# MCU.net
KiCad netlist of a schematic drawn in Altium Designer
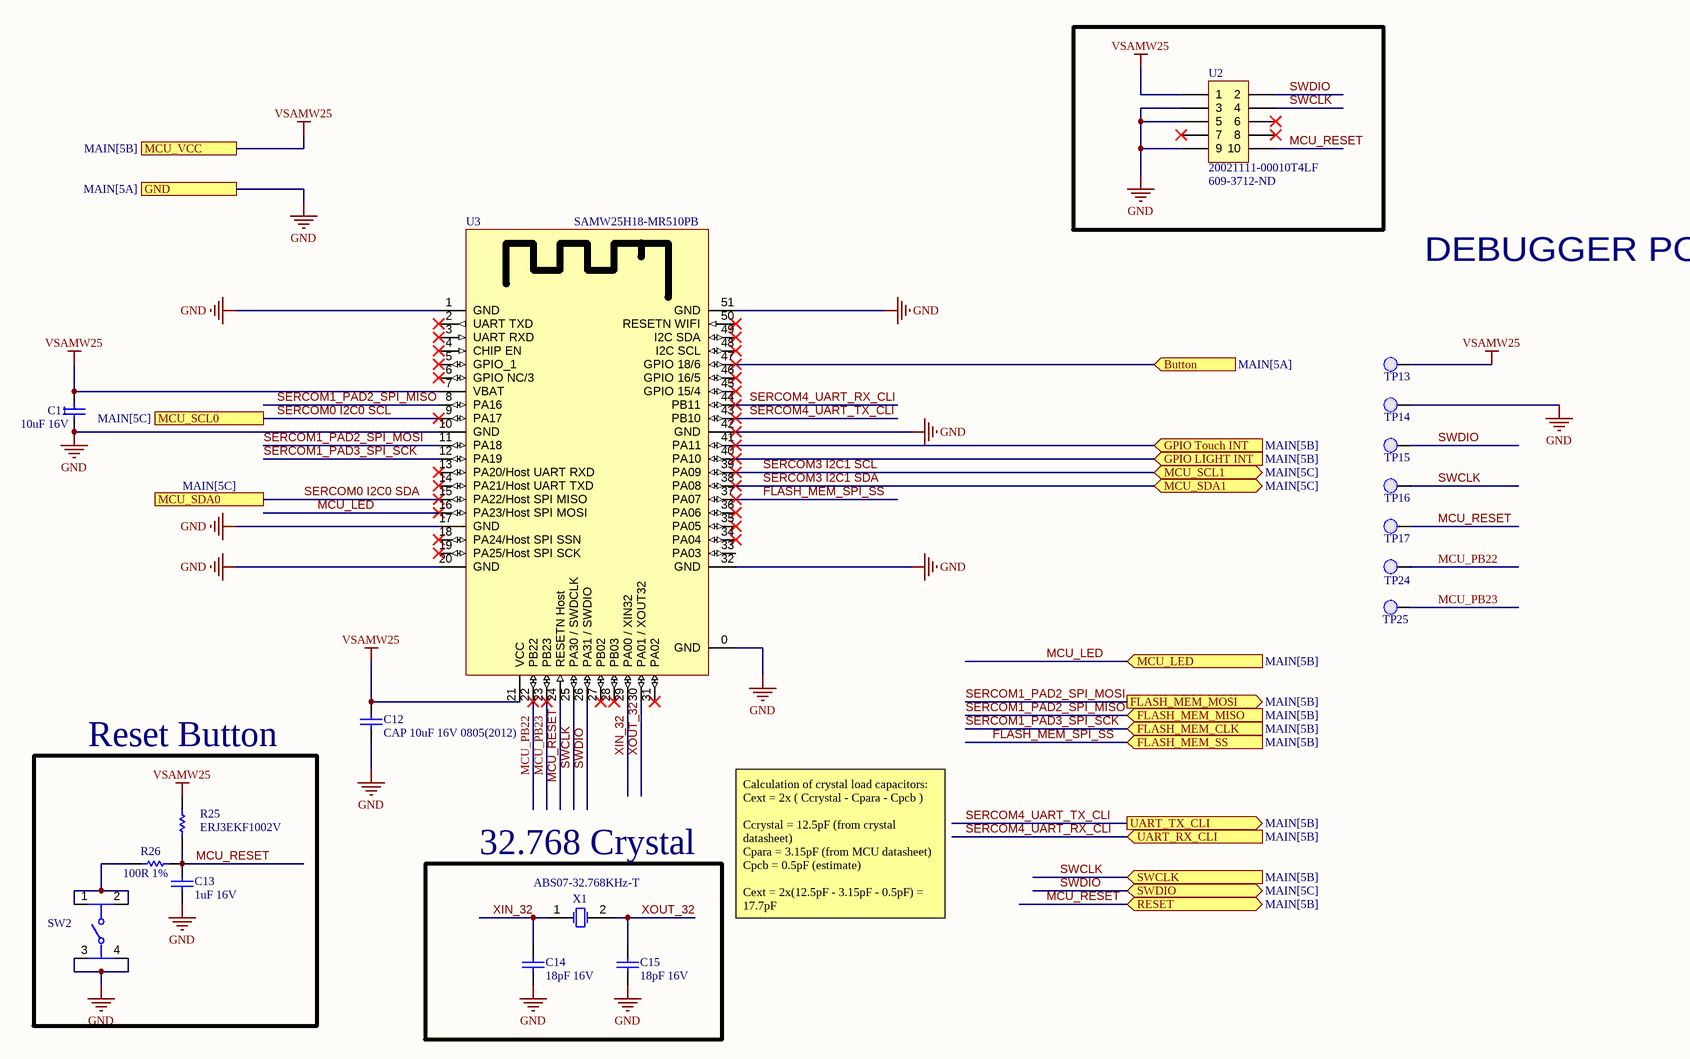
[diagram p0: MCU.SchDoc]

(export (version "E")
  (design (tool "Eeschema 10.0.6"))
  (components
    (comp (ref "C11")
      (value "10uF 16V")
      (footprint "CAPC0805(2012)145_N")
      (description "CAP 10uF 16V ±10% 0805 (2012 Metric) Thickness 1.45mm SMD")
      (fields (field (name "TOLERANCE") "Â±10%"))
      (libsource (lib "Altium Content Vault") (part "CAP"))
    )
    (comp (ref "C12")
      (value "CAP 10uF 16V 0805(2012)")
      (footprint "CAPC0805(2012)145_N")
      (description "CAP 10uF 16V ±10% 0805 (2012 Metric) Thickness 1.45mm SMD")
      (fields (field (name "TOLERANCE") "Â±10%"))
      (libsource (lib "Altium Content Vault") (part "CAP"))
    )
    (comp (ref "C13")
      (value "1uF 16V")
      (footprint "CAPC0603(1608)100_N")
      (description "CAP 1uF 16V ±5% 0603 (1608 Metric) Thickness 1mm SMD")
      (fields (field (name "TOLERANCE") "Â±5%"))
      (libsource (lib "Altium Content Vault") (part "CAP"))
    )
    (comp (ref "C14")
      (value "18pF 16V")
      (footprint "CAPC0603(1608)100_N")
      (description "CAP 18pF 16V ±5% 0603 (1608 Metric) Thickness 1mm SMD")
      (fields (field (name "TOLERANCE") "Â±5%"))
      (libsource (lib "Altium Content Vault") (part "CAP"))
    )
    (comp (ref "C15")
      (value "18pF 16V")
      (footprint "CAPC0603(1608)100_N")
      (description "CAP 18pF 16V ±5% 0603 (1608 Metric) Thickness 1mm SMD")
      (fields (field (name "TOLERANCE") "Â±5%"))
      (libsource (lib "Altium Content Vault") (part "CAP"))
    )
    (comp (ref "R25")
      (value "ERJ3EKF1002V")
      (footprint "RESC1609X55X30LL15T15")
      (description "Chip Resistor, 10 KOhm, +/- 1%, 0.1 W, -55 to 155 degC, 0603 (1608 Metric), RoHS, Tape and Reel")
      (fields (field (name "TOLERANCE") "1%") (field (name "MANUFACTURER") "Panasonic"))
      (libsource (lib "Altium Content Vault") (part "RES-2"))
    )
    (comp (ref "R26")
      (value "100R 1%")
      (footprint "RESC0603(1608)_N")
      (description "100R 0.1W 1% 0603 (1608 Metric)  SMD")
      (fields (field (name "TOLERANCE") "1 %") (field (name "POWER") "0.1 W"))
      (libsource (lib "Altium Content Vault") (part "RES"))
    )
    (comp (ref "SW2")
      (value "PTS810 SJG 250 SMTR LFS")
      (footprint "FP-PTS810_SJG_250_SMTR_LF-MFG")
      (description "SWITCH TACTILE SPST-NO 0.05A 16V")
      (fields
        (field (name "MANUFACTURER") "C&K Components")
        (field (name "OCTOPART") "https://octopart.com/pts810sjg250smtrlfs-c%26k+components-29380277")
      )
      (libsource (lib "Altium Content Vault") (part "1adf0dd01260c80cf25a44bfd6b99ba"))
    )
    (comp (ref "TP13")
      (value "0.1\" Pad")
      (footprint "PCBComponent")
      (libsource (lib "Components - 12.02.20 - 18.05") (part "0.1{dblquote} Pad-A.4"))
    )
    (comp (ref "TP14")
      (value "0.1\" Pad")
      (footprint "PCBComponent")
      (libsource (lib "Components - 12.02.20 - 18.05") (part "0.1{dblquote} Pad-A.4"))
    )
    (comp (ref "TP15")
      (value "0.1\" Pad")
      (footprint "PCBComponent")
      (libsource (lib "Components - 12.02.20 - 18.05") (part "0.1{dblquote} Pad-A.4"))
    )
    (comp (ref "TP16")
      (value "0.1\" Pad")
      (footprint "PCBComponent")
      (libsource (lib "Components - 12.02.20 - 18.05") (part "0.1{dblquote} Pad-A.4"))
    )
    (comp (ref "TP17")
      (value "0.1\" Pad")
      (footprint "PCBComponent")
      (libsource (lib "Components - 12.02.20 - 18.05") (part "0.1{dblquote} Pad-A.4"))
    )
    (comp (ref "TP24")
      (value "0.1\" Pad")
      (footprint "PCBComponent")
      (libsource (lib "Components - 12.02.20 - 18.05") (part "0.1{dblquote} Pad-A.4"))
    )
    (comp (ref "TP25")
      (value "0.1\" Pad")
      (footprint "PCBComponent")
      (libsource (lib "Components - 12.02.20 - 18.05") (part "0.1{dblquote} Pad-A.4"))
    )
    (comp (ref "U2")
      (value "20021111-00010T4LF")
      (footprint "20021111-00010T4LF")
      (description "CONN HEADER 10POS UNSHD VERT T/H")
      (fields
        (field (name "MANUFACTURER") "Amphenol / FCI")
        (field (name "SUPPLIER PART NUMBER 1") "609-3712-ND")
      )
      (libsource (lib "Schematics") (part "20021111-00010T4LF"))
    )
    (comp (ref "U3")
      (value "SAMW25H18-MR510PB")
      (footprint "SAMW25H18-MR510PB")
      (description "RF TXRX MODULE WIFI TRACE ANT")
      (fields
        (field (name "MANUFACTURER") "Atmel")
        (field (name "MANUFACTURER PART NUMBER") "ATSAMW25H18-MR510PB")
      )
      (libsource (lib "Schematics") (part "SAMW25H18-MR510PB"))
    )
    (comp (ref "X1")
      (value "ABS07-32.768KHz-T")
      (footprint "ABRA-ABS07-2_V")
      (description "Crystal, 32.768 kHz, 12.5 pF, -40 to 85 degC, SMD Low Profile 3.2 x 1.5 x 0.9 mm, Tape and Reel")
      (fields (field (name "MANUFACTURER") "Abracon"))
      (libsource (lib "Altium Content Vault") (part "ABRA-ABS07-2"))
    )
  )
  (nets
    (net (code "1") (name "/Button") (class "Default")
      (node (ref "U3") (pin "47") (pinfunction "GPIO_18/6_47") (pintype "bidirectional+no_connect"))
    )
    (net (code "2") (name "/FLASH_MEM_SPI_SS") (class "Default")
      (node (ref "U3") (pin "37") (pinfunction "PA07_37") (pintype "bidirectional+no_connect"))
    )
    (net (code "3") (name "/GPIO LIGHT INT") (class "Default")
      (node (ref "U3") (pin "40") (pinfunction "PA10_40") (pintype "bidirectional+no_connect"))
    )
    (net (code "4") (name "/GPIO Touch INT") (class "Default")
      (node (ref "U3") (pin "41") (pinfunction "PA11_41") (pintype "bidirectional+no_connect"))
    )
    (net (code "5") (name "/MCU_LED") (class "Default")
      (node (ref "U3") (pin "16") (pinfunction "PA23/Host_SPI_MOSI_16") (pintype "bidirectional+no_connect"))
    )
    (net (code "6") (name "/MCU_PB22") (class "Default")
      (node (ref "TP24") (pin "1") (pinfunction "PAD_1") (pintype "passive"))
      (node (ref "U3") (pin "22") (pinfunction "PB22_22") (pintype "bidirectional"))
    )
    (net (code "7") (name "/MCU_PB23") (class "Default")
      (node (ref "TP25") (pin "1") (pinfunction "PAD_1") (pintype "passive"))
      (node (ref "U3") (pin "23") (pinfunction "PB23_23") (pintype "bidirectional"))
    )
    (net (code "8") (name "/MCU_RESET") (class "Default")
      (node (ref "C13") (pin "2") (pinfunction "2_2") (pintype "passive"))
      (node (ref "R25") (pin "1") (pinfunction "1_1") (pintype "passive"))
      (node (ref "R26") (pin "2") (pinfunction "2_2") (pintype "passive"))
      (node (ref "TP17") (pin "1") (pinfunction "PAD_1") (pintype "passive"))
      (node (ref "U2") (pin "10") (pinfunction "10_10") (pintype "passive"))
      (node (ref "U3") (pin "24") (pinfunction "RESETN_Host_24") (pintype "input"))
    )
    (net (code "9") (name "/SERCOM0 I2C0 SCL") (class "Default")
      (node (ref "U3") (pin "9") (pinfunction "PA17_9") (pintype "bidirectional+no_connect"))
    )
    (net (code "10") (name "/SERCOM0 I2C0 SDA") (class "Default")
      (node (ref "U3") (pin "15") (pinfunction "PA22/Host_SPI_MISO_15") (pintype "bidirectional+no_connect"))
    )
    (net (code "11") (name "/SERCOM1_PAD2_SPI_MISO") (class "Default")
      (node (ref "U3") (pin "8") (pinfunction "PA16_8") (pintype "bidirectional"))
    )
    (net (code "12") (name "/SERCOM1_PAD2_SPI_MOSI") (class "Default")
      (node (ref "U3") (pin "11") (pinfunction "PA18_11") (pintype "bidirectional"))
    )
    (net (code "13") (name "/SERCOM1_PAD3_SPI_SCK") (class "Default")
      (node (ref "U3") (pin "12") (pinfunction "PA19_12") (pintype "bidirectional"))
    )
    (net (code "14") (name "/SERCOM3 I2C1 SCL") (class "Default")
      (node (ref "U3") (pin "39") (pinfunction "PA09_39") (pintype "bidirectional+no_connect"))
    )
    (net (code "15") (name "/SERCOM3 I2C1 SDA") (class "Default")
      (node (ref "U3") (pin "38") (pinfunction "PA08_38") (pintype "bidirectional+no_connect"))
    )
    (net (code "16") (name "/SERCOM4_UART_RX_CLI") (class "Default")
      (node (ref "U3") (pin "44") (pinfunction "PB11_44") (pintype "bidirectional+no_connect"))
    )
    (net (code "17") (name "/SERCOM4_UART_TX_CLI") (class "Default")
      (node (ref "U3") (pin "43") (pinfunction "PB10_43") (pintype "bidirectional+no_connect"))
    )
    (net (code "18") (name "/SWCLK") (class "Default")
      (node (ref "TP16") (pin "1") (pinfunction "PAD_1") (pintype "passive"))
      (node (ref "U2") (pin "4") (pinfunction "4_4") (pintype "passive"))
      (node (ref "U3") (pin "25") (pinfunction "PA30_/_SWDCLK_25") (pintype "bidirectional"))
    )
    (net (code "19") (name "/SWDIO") (class "Default")
      (node (ref "TP15") (pin "1") (pinfunction "PAD_1") (pintype "passive"))
      (node (ref "U2") (pin "2") (pinfunction "2_2") (pintype "passive"))
      (node (ref "U3") (pin "26") (pinfunction "PA31_/_SWDIO_26") (pintype "bidirectional"))
    )
    (net (code "20") (name "/XIN_32") (class "Default")
      (node (ref "C14") (pin "2") (pinfunction "2_2") (pintype "passive"))
      (node (ref "U3") (pin "29") (pinfunction "PA00_/_XIN32_29") (pintype "bidirectional"))
      (node (ref "X1") (pin "1") (pinfunction "X1_1") (pintype "passive"))
    )
    (net (code "21") (name "/XOUT_32") (class "Default")
      (node (ref "C15") (pin "2") (pinfunction "2_2") (pintype "passive"))
      (node (ref "U3") (pin "30") (pinfunction "PA01_/_XOUT32_30") (pintype "bidirectional"))
      (node (ref "X1") (pin "2") (pinfunction "X2_2") (pintype "passive"))
    )
    (net (code "22") (name "GND") (class "Default")
      (node (ref "C11") (pin "1") (pinfunction "1_1") (pintype "passive"))
      (node (ref "C12") (pin "1") (pinfunction "1_1") (pintype "passive"))
      (node (ref "C13") (pin "1") (pinfunction "1_1") (pintype "passive"))
      (node (ref "C14") (pin "1") (pinfunction "1_1") (pintype "passive"))
      (node (ref "C15") (pin "1") (pinfunction "1_1") (pintype "passive"))
      (node (ref "SW2") (pin "3") (pinfunction "3_3") (pintype "passive"))
      (node (ref "SW2") (pin "4") (pinfunction "4_4") (pintype "passive"))
      (node (ref "TP14") (pin "1") (pinfunction "PAD_1") (pintype "passive"))
      (node (ref "U2") (pin "3") (pinfunction "3_3") (pintype "passive"))
      (node (ref "U2") (pin "5") (pinfunction "5_5") (pintype "passive"))
      (node (ref "U2") (pin "9") (pinfunction "9_9") (pintype "passive"))
      (node (ref "U3") (pin "0") (pinfunction "GND_0") (pintype "power_in"))
      (node (ref "U3") (pin "1") (pinfunction "GND_1") (pintype "power_in"))
      (node (ref "U3") (pin "10") (pinfunction "GND_10") (pintype "power_in"))
      (node (ref "U3") (pin "17") (pinfunction "GND_17") (pintype "power_in"))
      (node (ref "U3") (pin "20") (pinfunction "GND_20") (pintype "power_in"))
      (node (ref "U3") (pin "32") (pinfunction "GND_32") (pintype "power_in"))
      (node (ref "U3") (pin "42") (pinfunction "GND_42") (pintype "power_in"))
      (node (ref "U3") (pin "51") (pinfunction "GND_51") (pintype "power_in"))
    )
    (net (code "23") (name "Net-(R26-Pad1)") (class "Default")
      (node (ref "R26") (pin "1") (pinfunction "1_1") (pintype "passive"))
      (node (ref "SW2") (pin "1") (pinfunction "1_1") (pintype "passive"))
      (node (ref "SW2") (pin "2") (pinfunction "2_2") (pintype "passive"))
    )
    (net (code "24") (name "VSAMW25") (class "Default")
      (node (ref "C11") (pin "2") (pinfunction "2_2") (pintype "passive"))
      (node (ref "C12") (pin "2") (pinfunction "2_2") (pintype "passive"))
      (node (ref "R25") (pin "2") (pinfunction "2_2") (pintype "passive"))
      (node (ref "TP13") (pin "1") (pinfunction "PAD_1") (pintype "passive"))
      (node (ref "U2") (pin "1") (pinfunction "1_1") (pintype "passive"))
      (node (ref "U3") (pin "21") (pinfunction "VCC_21") (pintype "power_in"))
      (node (ref "U3") (pin "7") (pinfunction "VBAT_7") (pintype "power_in"))
    )
    (net (code "25") (name "unconnected-(U2-Pad6)") (class "Default")
      (node (ref "U2") (pin "6") (pinfunction "6_6") (pintype "passive+no_connect"))
    )
    (net (code "26") (name "unconnected-(U2-Pad7)") (class "Default")
      (node (ref "U2") (pin "7") (pinfunction "7_7") (pintype "passive+no_connect"))
    )
    (net (code "27") (name "unconnected-(U2-Pad8)") (class "Default")
      (node (ref "U2") (pin "8") (pinfunction "8_8") (pintype "passive+no_connect"))
    )
    (net (code "28") (name "unconnected-(U3-CHIP_EN-Pad4)") (class "Default")
      (node (ref "U3") (pin "4") (pinfunction "CHIP_EN_4") (pintype "input+no_connect"))
    )
    (net (code "29") (name "unconnected-(U3-GPIO_1-Pad5)") (class "Default")
      (node (ref "U3") (pin "5") (pinfunction "GPIO_1_5") (pintype "bidirectional+no_connect"))
    )
    (net (code "30") (name "unconnected-(U3-GPIO_15{slash}4-Pad45)") (class "Default")
      (node (ref "U3") (pin "45") (pinfunction "GPIO_15/4_45") (pintype "bidirectional+no_connect"))
    )
    (net (code "31") (name "unconnected-(U3-GPIO_16{slash}5-Pad46)") (class "Default")
      (node (ref "U3") (pin "46") (pinfunction "GPIO_16/5_46") (pintype "bidirectional+no_connect"))
    )
    (net (code "32") (name "unconnected-(U3-GPIO_NC{slash}3-Pad6)") (class "Default")
      (node (ref "U3") (pin "6") (pinfunction "GPIO_NC/3_6") (pintype "bidirectional+no_connect"))
    )
    (net (code "33") (name "unconnected-(U3-I2C_SCL-Pad48)") (class "Default")
      (node (ref "U3") (pin "48") (pinfunction "I2C_SCL_48") (pintype "bidirectional+no_connect"))
    )
    (net (code "34") (name "unconnected-(U3-I2C_SDA-Pad49)") (class "Default")
      (node (ref "U3") (pin "49") (pinfunction "I2C_SDA_49") (pintype "bidirectional+no_connect"))
    )
    (net (code "35") (name "unconnected-(U3-PA02-Pad31)") (class "Default")
      (node (ref "U3") (pin "31") (pinfunction "PA02_31") (pintype "bidirectional+no_connect"))
    )
    (net (code "36") (name "unconnected-(U3-PA03-Pad33)") (class "Default")
      (node (ref "U3") (pin "33") (pinfunction "PA03_33") (pintype "bidirectional"))
    )
    (net (code "37") (name "unconnected-(U3-PA04-Pad34)") (class "Default")
      (node (ref "U3") (pin "34") (pinfunction "PA04_34") (pintype "bidirectional+no_connect"))
    )
    (net (code "38") (name "unconnected-(U3-PA05-Pad35)") (class "Default")
      (node (ref "U3") (pin "35") (pinfunction "PA05_35") (pintype "bidirectional+no_connect"))
    )
    (net (code "39") (name "unconnected-(U3-PA06-Pad36)") (class "Default")
      (node (ref "U3") (pin "36") (pinfunction "PA06_36") (pintype "bidirectional+no_connect"))
    )
    (net (code "40") (name "unconnected-(U3-PA20{slash}Host_UART_RXD-Pad13)") (class "Default")
      (node (ref "U3") (pin "13") (pinfunction "PA20/Host_UART_RXD_13") (pintype "bidirectional+no_connect"))
    )
    (net (code "41") (name "unconnected-(U3-PA21{slash}Host_UART_TXD-Pad14)") (class "Default")
      (node (ref "U3") (pin "14") (pinfunction "PA21/Host_UART_TXD_14") (pintype "bidirectional+no_connect"))
    )
    (net (code "42") (name "unconnected-(U3-PA24{slash}Host_SPI_SSN-Pad18)") (class "Default")
      (node (ref "U3") (pin "18") (pinfunction "PA24/Host_SPI_SSN_18") (pintype "bidirectional+no_connect"))
    )
    (net (code "43") (name "unconnected-(U3-PA25{slash}Host_SPI_SCK-Pad19)") (class "Default")
      (node (ref "U3") (pin "19") (pinfunction "PA25/Host_SPI_SCK_19") (pintype "bidirectional+no_connect"))
    )
    (net (code "44") (name "unconnected-(U3-PB02-Pad27)") (class "Default")
      (node (ref "U3") (pin "27") (pinfunction "PB02_27") (pintype "bidirectional+no_connect"))
    )
    (net (code "45") (name "unconnected-(U3-PB03-Pad28)") (class "Default")
      (node (ref "U3") (pin "28") (pinfunction "PB03_28") (pintype "bidirectional+no_connect"))
    )
    (net (code "46") (name "unconnected-(U3-RESETN_WIFI-Pad50)") (class "Default")
      (node (ref "U3") (pin "50") (pinfunction "RESETN_WIFI_50") (pintype "input+no_connect"))
    )
    (net (code "47") (name "unconnected-(U3-UART_RXD-Pad3)") (class "Default")
      (node (ref "U3") (pin "3") (pinfunction "UART_RXD_3") (pintype "input+no_connect"))
    )
    (net (code "48") (name "unconnected-(U3-UART_TXD-Pad2)") (class "Default")
      (node (ref "U3") (pin "2") (pinfunction "UART_TXD_2") (pintype "output+no_connect"))
    )
  )
)
